# usb_ethernet.net
KiCad netlist of a schematic drawn in Altium Designer
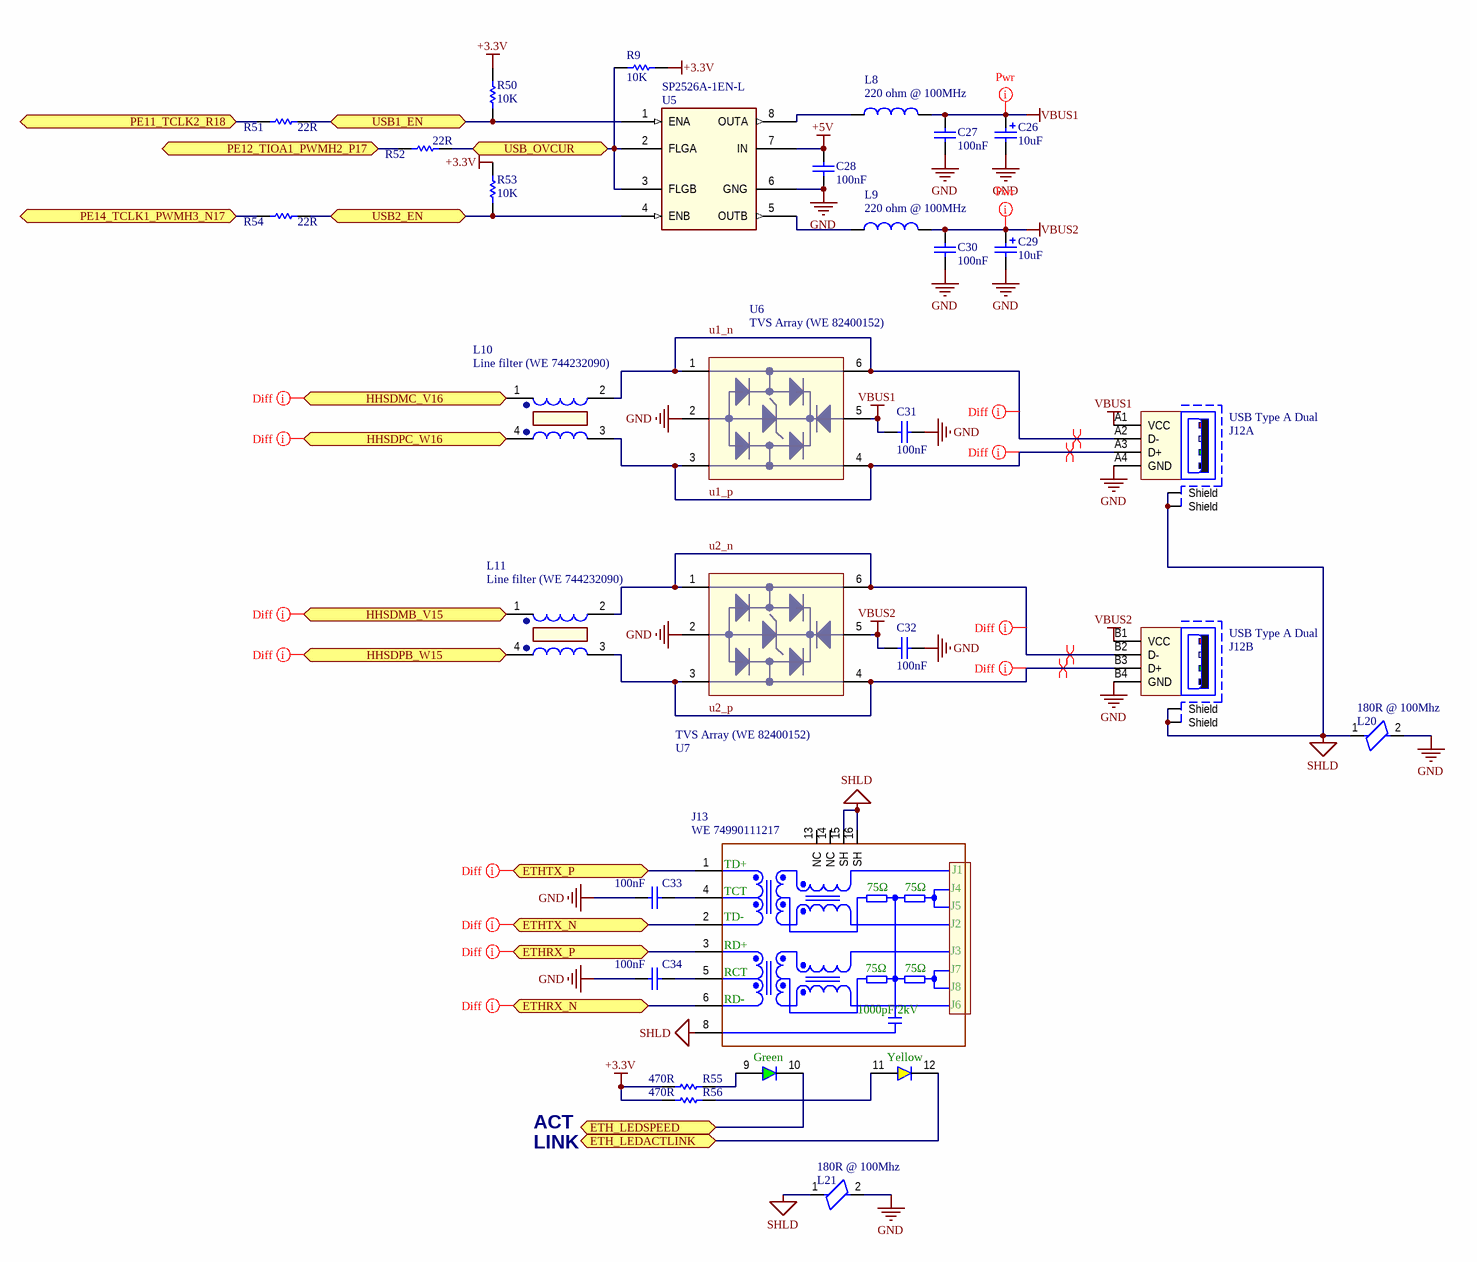
[diagram p0: usb_ethernet.SchDoc]

(export (version "E")
  (design (tool "Eeschema 10.0.6"))
  (components
    (comp (ref "C26")
      (value "10uF")
      (footprint "1206_[3216]")
      (description "Ceramic X5R 25V")
      (fields (field (name "PUBLISHER") "Altium Limited"))
      (libsource (lib "DEVELER_Library") (part "Cap Pol1"))
    )
    (comp (ref "C27")
      (value "100nF")
      (footprint "0603_[1608]")
      (description "Ceramic X7R 50V")
      (fields (field (name "PUBLISHER") "Altium Limited"))
      (libsource (lib "Miscellaneous Devices") (part "Cap"))
    )
    (comp (ref "C28")
      (value "100nF")
      (footprint "0603_[1608]")
      (description "Ceramic X7R 50V")
      (fields (field (name "PUBLISHER") "Altium Limited"))
      (libsource (lib "Miscellaneous Devices") (part "Cap"))
    )
    (comp (ref "C29")
      (value "10uF")
      (footprint "1206_[3216]")
      (description "Ceramic X5R 25V")
      (fields (field (name "PUBLISHER") "Altium Limited"))
      (libsource (lib "DEVELER_Library") (part "Cap Pol1"))
    )
    (comp (ref "C30")
      (value "100nF")
      (footprint "0603_[1608]")
      (description "Ceramic X7R 50V")
      (fields (field (name "PUBLISHER") "Altium Limited"))
      (libsource (lib "Miscellaneous Devices") (part "Cap"))
    )
    (comp (ref "C31")
      (value "100nF")
      (footprint "0603_[1608]")
      (description "Ceramic X7R 50V")
      (fields (field (name "PUBLISHER") "Altium Limited"))
      (libsource (lib "Miscellaneous Devices") (part "Cap"))
    )
    (comp (ref "C32")
      (value "100nF")
      (footprint "0603_[1608]")
      (description "Ceramic X7R 50V")
      (fields (field (name "PUBLISHER") "Altium Limited"))
      (libsource (lib "Miscellaneous Devices") (part "Cap"))
    )
    (comp (ref "C33")
      (value "100nF")
      (footprint "0603_[1608]")
      (description "Ceramic X7R 50V")
      (fields (field (name "PUBLISHER") "Altium Limited"))
      (libsource (lib "project42_lib") (part "Cap"))
    )
    (comp (ref "C34")
      (value "100nF")
      (footprint "0603_[1608]")
      (description "Ceramic X7R 50V")
      (fields (field (name "PUBLISHER") "Altium Limited"))
      (libsource (lib "project42_lib") (part "Cap"))
    )
    (comp (ref "J12")
      (value "USB Type A Dual")
      (footprint "USB_TypeA_Double_THD")
      (description "USB Type-A Double Connector (WE  61400826021)")
      (fields
        (field (name "MANUFACTURER") "Würth Elektronik eiSos GmbH")
        (field (name "PARTNO") "61400826021")
        (field (name "CREATED BY") "Karrer Zheng")
      )
      (libsource (lib "61400826021") (part "WE-Communication Connectors 61400826021"))
    )
    (comp (ref "J13")
      (value "WE 74990111217")
      (footprint "RJ45_lan_transformer_horizontal")
      (description "Integrated RJ45 Transformer WE-RJ45LAN (WE 74990111217)")
      (fields
        (field (name "PARTNO") "74980111211")
        (field (name "MANUFACTURER") "Wurth Elektronik")
        (field (name "CREATED BY") "Karrer Zheng")
        (field (name "E-MAIL") "libraries@we-online.com")
      )
      (libsource (lib "DEVELER_Library") (part "RJ45LAN-10/100BaseT"))
    )
    (comp (ref "L8")
      (value "220 ohm @ 100MHz")
      (footprint "0805_[2012]")
      (description "WE 742792022")
      (libsource (lib "DEVELER_Library") (part "Inductor"))
    )
    (comp (ref "L9")
      (value "220 ohm @ 100MHz")
      (footprint "0805_[2012]")
      (description "WE 742792022")
      (libsource (lib "DEVELER_Library") (part "Inductor"))
    )
    (comp (ref "L10")
      (value "Line filter (WE 744232090)")
      (footprint "WE-CNSW_1206")
      (description "Common mode line filter")
      (libsource (lib "DEVELER_Library") (part "Common_mode_choke"))
    )
    (comp (ref "L11")
      (value "Line filter (WE 744232090)")
      (footprint "WE-CNSW_1206")
      (description "Common mode line filter")
      (libsource (lib "DEVELER_Library") (part "Common_mode_choke"))
    )
    (comp (ref "L20")
      (value "180R @ 100Mhz")
      (footprint "0603_[1608]")
      (description "Ferrite Beat (WE 7427927218)")
      (libsource (lib "project42_lib") (part "BEAD_ FERRITE"))
    )
    (comp (ref "L21")
      (value "180R @ 100Mhz")
      (footprint "0603_[1608]")
      (description "Ferrite Beat (WE 7427927218)")
      (libsource (lib "project42_lib") (part "BEAD_ FERRITE"))
    )
    (comp (ref "R9")
      (value "10K")
      (footprint "0603_[1608]")
      (description "Resistor")
      (fields (field (name "PUBLISHER") "Altium Limited"))
      (libsource (lib "DEVELER_Library") (part "Res1"))
    )
    (comp (ref "R50")
      (value "10K")
      (footprint "0603_[1608]")
      (description "Resistor")
      (fields (field (name "PUBLISHER") "Altium Limited"))
      (libsource (lib "DEVELER_Library") (part "Res1"))
    )
    (comp (ref "R51")
      (value "22R")
      (footprint "0603_[1608]")
      (description "Resistor")
      (fields (field (name "PUBLISHER") "Altium Limited"))
      (libsource (lib "DEVELER_Library") (part "Res1"))
    )
    (comp (ref "R52")
      (value "22R")
      (footprint "0603_[1608]")
      (description "Resistor")
      (fields (field (name "PUBLISHER") "Altium Limited"))
      (libsource (lib "DEVELER_Library") (part "Res1"))
    )
    (comp (ref "R53")
      (value "10K")
      (footprint "0603_[1608]")
      (description "Resistor")
      (fields (field (name "PUBLISHER") "Altium Limited"))
      (libsource (lib "DEVELER_Library") (part "Res1"))
    )
    (comp (ref "R54")
      (value "22R")
      (footprint "0603_[1608]")
      (description "Resistor")
      (fields (field (name "PUBLISHER") "Altium Limited"))
      (libsource (lib "DEVELER_Library") (part "Res1"))
    )
    (comp (ref "R55")
      (value "470R")
      (footprint "0603_[1608]")
      (description "Resistor")
      (fields (field (name "PUBLISHER") "Altium Limited"))
      (libsource (lib "DEVELER_Library") (part "Res1"))
    )
    (comp (ref "R56")
      (value "470R")
      (footprint "0603_[1608]")
      (description "Resistor")
      (fields (field (name "PUBLISHER") "Altium Limited"))
      (libsource (lib "DEVELER_Library") (part "Res1"))
    )
    (comp (ref "U5")
      (value "SP2526A-1EN-L")
      (footprint "SOIC8")
      (description "USB Power Supply swtich HI-SIDE dual.")
      (libsource (lib "DEVELER_Library") (part "SP2526A-1EN-L"))
    )
    (comp (ref "U6")
      (value "TVS Array (WE 82400152)")
      (footprint "SOT-563")
      (libsource (lib "DEVELER_Library") (part "TVS_Diode_Array"))
    )
    (comp (ref "U7")
      (value "TVS Array (WE 82400152)")
      (footprint "SOT-563")
      (libsource (lib "DEVELER_Library") (part "TVS_Diode_Array"))
    )
  )
  (nets
    (net (code "1") (name "+3.3V") (class "Default")
      (node (ref "R50") (pin "1") (pinfunction "1_1") (pintype "passive"))
      (node (ref "R53") (pin "1") (pinfunction "1_1") (pintype "passive"))
      (node (ref "R55") (pin "2") (pinfunction "2_2") (pintype "passive"))
      (node (ref "R56") (pin "2") (pinfunction "2_2") (pintype "passive"))
      (node (ref "R9") (pin "1") (pinfunction "1_1") (pintype "passive"))
    )
    (net (code "2") (name "+5V") (class "Default")
      (node (ref "C28") (pin "1") (pinfunction "1_1") (pintype "passive"))
      (node (ref "U5") (pin "7") (pinfunction "IN_7") (pintype "power_in"))
    )
    (net (code "3") (name "/ETHRX_N") (class "Default")
      (node (ref "J13") (pin "6") (pinfunction "RD-_6") (pintype "passive"))
    )
    (net (code "4") (name "/ETHRX_P") (class "Default")
      (node (ref "J13") (pin "3") (pinfunction "RD+_3") (pintype "passive"))
    )
    (net (code "5") (name "/ETHTX_N") (class "Default")
      (node (ref "J13") (pin "2") (pinfunction "TD-_2") (pintype "passive"))
    )
    (net (code "6") (name "/ETHTX_P") (class "Default")
      (node (ref "J13") (pin "1") (pinfunction "TD+_1") (pintype "passive"))
    )
    (net (code "7") (name "/ETH_LEDACTLINK") (class "Default")
      (node (ref "J13") (pin "12") (pinfunction "Kg_12") (pintype "passive"))
    )
    (net (code "8") (name "/ETH_LEDSPEED") (class "Default")
      (node (ref "J13") (pin "10") (pinfunction "Ky_10") (pintype "passive"))
    )
    (net (code "9") (name "/HHSDMB_V15") (class "Default")
      (node (ref "L11") (pin "1") (pinfunction "1_1") (pintype "passive"))
    )
    (net (code "10") (name "/HHSDMC_V16") (class "Default")
      (node (ref "L10") (pin "1") (pinfunction "1_1") (pintype "passive"))
    )
    (net (code "11") (name "/HHSDPB_W15") (class "Default")
      (node (ref "L11") (pin "4") (pinfunction "4_4") (pintype "passive"))
    )
    (net (code "12") (name "/HHSDPC_W16") (class "Default")
      (node (ref "L10") (pin "4") (pinfunction "4_4") (pintype "passive"))
    )
    (net (code "13") (name "/PE11_TCLK2_R18") (class "Default")
      (node (ref "R51") (pin "1") (pinfunction "1_1") (pintype "passive"))
    )
    (net (code "14") (name "/PE12_TIOA1_PWMH2_P17") (class "Default")
      (node (ref "R52") (pin "1") (pinfunction "1_1") (pintype "passive"))
    )
    (net (code "15") (name "/PE14_TCLK1_PWMH3_N17") (class "Default")
      (node (ref "R54") (pin "1") (pinfunction "1_1") (pintype "passive"))
    )
    (net (code "16") (name "/USB1_EN") (class "Default")
      (node (ref "R50") (pin "2") (pinfunction "2_2") (pintype "passive"))
      (node (ref "R51") (pin "2") (pinfunction "2_2") (pintype "passive"))
      (node (ref "U5") (pin "1") (pinfunction "ENA_1") (pintype "input"))
    )
    (net (code "17") (name "/USB2_EN") (class "Default")
      (node (ref "R53") (pin "2") (pinfunction "2_2") (pintype "passive"))
      (node (ref "R54") (pin "2") (pinfunction "2_2") (pintype "passive"))
      (node (ref "U5") (pin "4") (pinfunction "ENB_4") (pintype "input"))
    )
    (net (code "18") (name "/USB_OVCUR") (class "Default")
      (node (ref "R52") (pin "2") (pinfunction "2_2") (pintype "passive"))
      (node (ref "R9") (pin "2") (pinfunction "2_2") (pintype "passive"))
      (node (ref "U5") (pin "2") (pinfunction "FLGA_2") (pintype "open_collector"))
      (node (ref "U5") (pin "3") (pinfunction "FLGB_3") (pintype "open_collector"))
    )
    (net (code "19") (name "/u1_n") (class "Default")
      (node (ref "J12") (pin "A2") (pinfunction "D-_A2") (pintype "passive"))
      (node (ref "L10") (pin "2") (pinfunction "2_2") (pintype "passive"))
      (node (ref "U6") (pin "1") (pinfunction "1_1") (pintype "passive"))
      (node (ref "U6") (pin "6") (pinfunction "6_6") (pintype "passive"))
    )
    (net (code "20") (name "/u1_p") (class "Default")
      (node (ref "J12") (pin "A3") (pinfunction "D+_A3") (pintype "passive"))
      (node (ref "L10") (pin "3") (pinfunction "3_3") (pintype "passive"))
      (node (ref "U6") (pin "3") (pinfunction "3_3") (pintype "passive"))
      (node (ref "U6") (pin "4") (pinfunction "4_4") (pintype "passive"))
    )
    (net (code "21") (name "/u2_n") (class "Default")
      (node (ref "J12") (pin "B2") (pinfunction "D-_B2") (pintype "passive"))
      (node (ref "L11") (pin "2") (pinfunction "2_2") (pintype "passive"))
      (node (ref "U7") (pin "1") (pinfunction "1_1") (pintype "passive"))
      (node (ref "U7") (pin "6") (pinfunction "6_6") (pintype "passive"))
    )
    (net (code "22") (name "/u2_p") (class "Default")
      (node (ref "J12") (pin "B3") (pinfunction "D+_B3") (pintype "passive"))
      (node (ref "L11") (pin "3") (pinfunction "3_3") (pintype "passive"))
      (node (ref "U7") (pin "3") (pinfunction "3_3") (pintype "passive"))
      (node (ref "U7") (pin "4") (pinfunction "4_4") (pintype "passive"))
    )
    (net (code "23") (name "GND") (class "Default")
      (node (ref "C26") (pin "2") (pinfunction "2_2") (pintype "passive"))
      (node (ref "C27") (pin "2") (pinfunction "2_2") (pintype "passive"))
      (node (ref "C28") (pin "2") (pinfunction "2_2") (pintype "passive"))
      (node (ref "C29") (pin "2") (pinfunction "2_2") (pintype "passive"))
      (node (ref "C30") (pin "2") (pinfunction "2_2") (pintype "passive"))
      (node (ref "C31") (pin "1") (pinfunction "1_1") (pintype "passive"))
      (node (ref "C32") (pin "1") (pinfunction "1_1") (pintype "passive"))
      (node (ref "C33") (pin "2") (pinfunction "2_2") (pintype "passive"))
      (node (ref "C34") (pin "2") (pinfunction "2_2") (pintype "passive"))
      (node (ref "J12") (pin "A4") (pinfunction "GND_A4") (pintype "passive"))
      (node (ref "J12") (pin "B4") (pinfunction "GND_B4") (pintype "passive"))
      (node (ref "L20") (pin "2") (pinfunction "2_2") (pintype "passive"))
      (node (ref "L21") (pin "2") (pinfunction "2_2") (pintype "passive"))
      (node (ref "U5") (pin "6") (pinfunction "GNG_6") (pintype "power_in"))
      (node (ref "U6") (pin "2") (pinfunction "2_2") (pintype "passive"))
      (node (ref "U7") (pin "2") (pinfunction "2_2") (pintype "passive"))
    )
    (net (code "24") (name "Net-(J13-Ag)") (class "Default")
      (node (ref "J13") (pin "11") (pinfunction "Ag_11") (pintype "passive"))
      (node (ref "R56") (pin "1") (pinfunction "1_1") (pintype "passive"))
    )
    (net (code "25") (name "Net-(J13-Ay)") (class "Default")
      (node (ref "J13") (pin "9") (pinfunction "Ay_9") (pintype "passive"))
      (node (ref "R55") (pin "1") (pinfunction "1_1") (pintype "passive"))
    )
    (net (code "26") (name "Net-(J13-RCT)") (class "Default")
      (node (ref "C34") (pin "1") (pinfunction "1_1") (pintype "passive"))
      (node (ref "J13") (pin "5") (pinfunction "RCT_5") (pintype "passive"))
    )
    (net (code "27") (name "Net-(J13-TCT)") (class "Default")
      (node (ref "C33") (pin "1") (pinfunction "1_1") (pintype "passive"))
      (node (ref "J13") (pin "4") (pinfunction "TCT_4") (pintype "passive"))
    )
    (net (code "28") (name "Net-(U5-OUTA)") (class "Default")
      (node (ref "L8") (pin "2") (pinfunction "2_2") (pintype "passive"))
      (node (ref "U5") (pin "8") (pinfunction "OUTA_8") (pintype "output"))
    )
    (net (code "29") (name "Net-(U5-OUTB)") (class "Default")
      (node (ref "L9") (pin "2") (pinfunction "2_2") (pintype "passive"))
      (node (ref "U5") (pin "5") (pinfunction "OUTB_5") (pintype "output"))
    )
    (net (code "30") (name "SHLD") (class "Default")
      (node (ref "J12") (pin "Z1") (pinfunction "Shield_Z1") (pintype "passive"))
      (node (ref "J12") (pin "Z2") (pinfunction "Shield_Z2") (pintype "passive"))
      (node (ref "J12") (pin "Z3") (pinfunction "Shield_Z3") (pintype "passive"))
      (node (ref "J12") (pin "Z4") (pinfunction "Shield_Z4") (pintype "passive"))
      (node (ref "J13") (pin "15") (pinfunction "SH_15") (pintype "passive"))
      (node (ref "J13") (pin "16") (pinfunction "SH_16") (pintype "passive"))
      (node (ref "J13") (pin "8") (pinfunction "SHLD_8") (pintype "passive"))
      (node (ref "L20") (pin "1") (pinfunction "1_1") (pintype "passive"))
      (node (ref "L21") (pin "1") (pinfunction "1_1") (pintype "passive"))
    )
    (net (code "31") (name "VBUS1") (class "Default")
      (node (ref "C26") (pin "1") (pinfunction "1_1") (pintype "passive"))
      (node (ref "C27") (pin "1") (pinfunction "1_1") (pintype "passive"))
      (node (ref "C31") (pin "2") (pinfunction "2_2") (pintype "passive"))
      (node (ref "J12") (pin "A1") (pinfunction "VCC_A1") (pintype "passive"))
      (node (ref "L8") (pin "1") (pinfunction "1_1") (pintype "passive"))
      (node (ref "U6") (pin "5") (pinfunction "5_5") (pintype "passive"))
    )
    (net (code "32") (name "VBUS2") (class "Default")
      (node (ref "C29") (pin "1") (pinfunction "1_1") (pintype "passive"))
      (node (ref "C30") (pin "1") (pinfunction "1_1") (pintype "passive"))
      (node (ref "C32") (pin "2") (pinfunction "2_2") (pintype "passive"))
      (node (ref "J12") (pin "B1") (pinfunction "VCC_B1") (pintype "passive"))
      (node (ref "L9") (pin "1") (pinfunction "1_1") (pintype "passive"))
      (node (ref "U7") (pin "5") (pinfunction "5_5") (pintype "passive"))
    )
    (net (code "33") (name "unconnected-(J13-NC-Pad13)") (class "Default")
      (node (ref "J13") (pin "13") (pinfunction "NC_13") (pintype "passive"))
    )
    (net (code "34") (name "unconnected-(J13-NC-Pad14)") (class "Default")
      (node (ref "J13") (pin "14") (pinfunction "NC_14") (pintype "passive"))
    )
  )
)
